# Dental_Sensor_-_CAP.net
KiCad netlist of a schematic drawn in Altium Designer
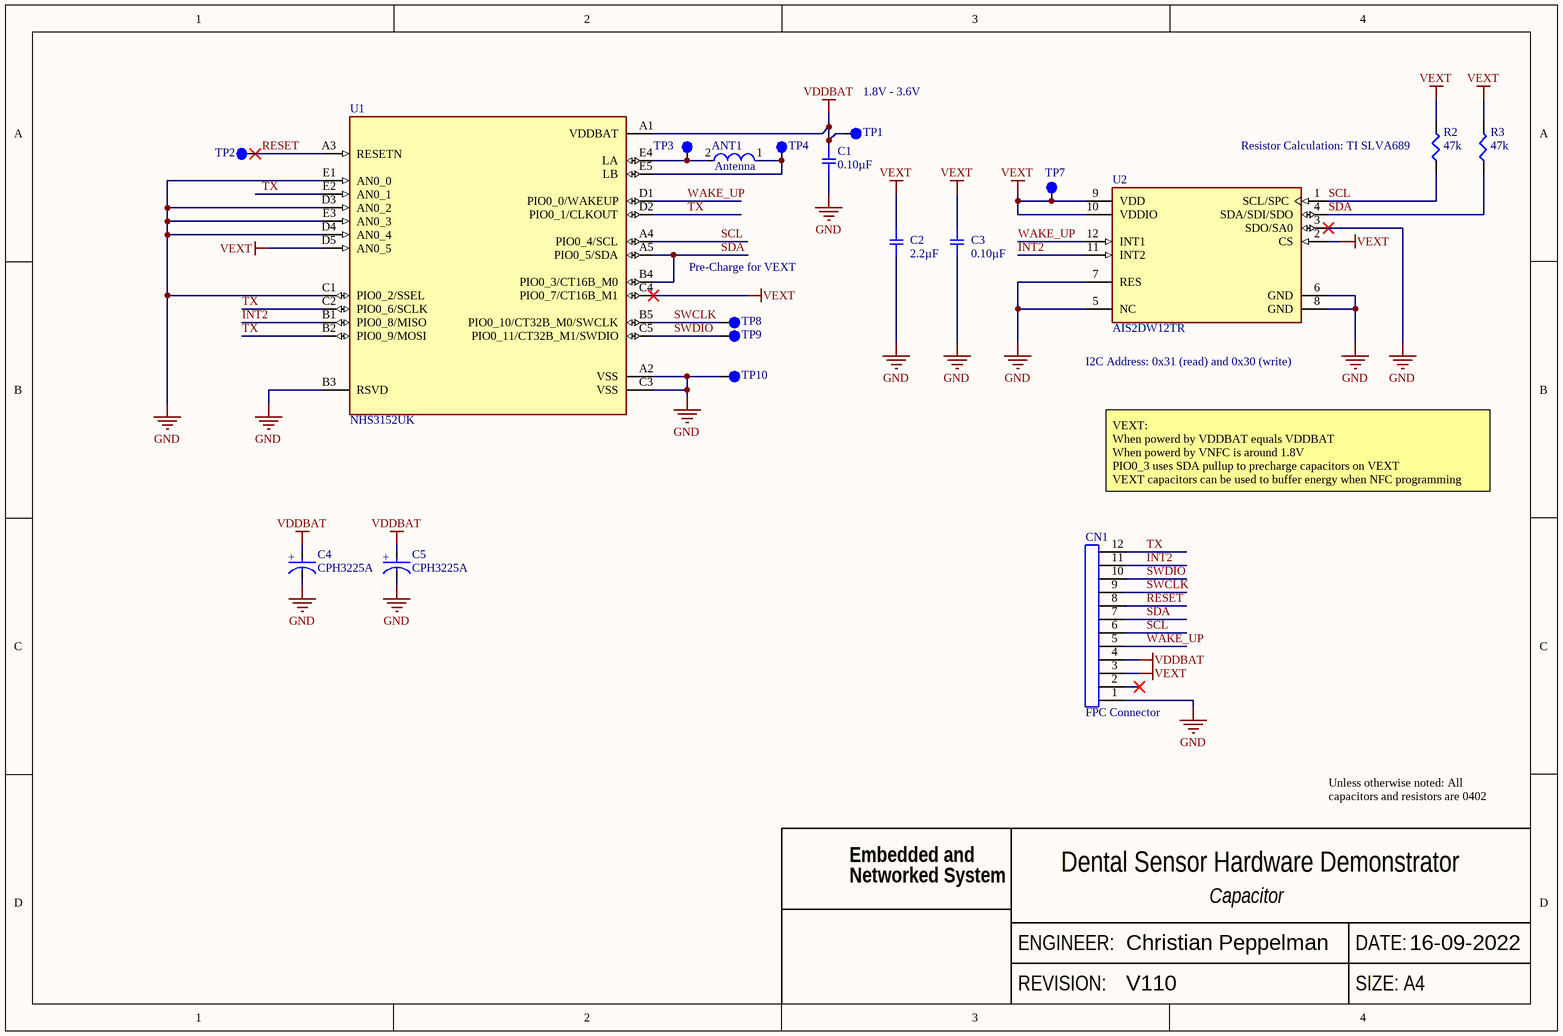
[diagram p0: Dental Sensor - CAP.SchDoc]

(export (version "E")
  (design (tool "Eeschema 10.0.6"))
  (components
    (comp (ref "ANT1")
      (value "Antenna")
      (footprint "NFC Antenna")
      (description "Track 0.2; Gap 0.1; Height 4.6; Width 14.5;")
      (libsource (lib "Library") (part "NFC Antenna"))
    )
    (comp (ref "C1")
      (value "0.10µF")
      (footprint "CAPC1005X03N")
      (description "CAP CER 0.1UF 6.3V X5R 0402")
      (fields
        (field (name "DIGI-KEY PART NUMBER") "490-6287-1-ND")
        (field (name "PART NUMBER") "GRM155R60J104KA01D")
      )
      (libsource (lib "capacitor_murata_0402") (part "GRM155R60J104KA01D"))
    )
    (comp (ref "C2")
      (value "2.2µF")
      (footprint "CAPC1005X03N")
      (description "CAP CER 2.2UF 6.3V X5R 0402")
      (fields
        (field (name "DIGI-KEY PART NUMBER") "490-12250-1-ND")
        (field (name "PART NUMBER") "GRT155R60J225KE01D")
      )
      (libsource (lib "capacitor_murata_0402") (part "GRT155R60J225KE01D"))
    )
    (comp (ref "C3")
      (value "0.10µF")
      (footprint "CAPC1005X03N")
      (description "CAP CER 0.1UF 6.3V X5R 0402")
      (fields
        (field (name "DIGI-KEY PART NUMBER") "490-6287-1-ND")
        (field (name "PART NUMBER") "GRM155R60J104KA01D")
      )
      (libsource (lib "capacitor_murata_0402") (part "GRM155R60J104KA01D"))
    )
    (comp (ref "C4")
      (value "CPH3225A")
      (footprint "CPH3225A")
      (description "Supercapacitors / Ultracapacitors Reflow EDLC 3.3V, 11mF, 160 Ohm")
      (libsource (lib "Library") (part "CPH3225A"))
    )
    (comp (ref "C5")
      (value "CPH3225A")
      (footprint "CPH3225A")
      (description "Supercapacitors / Ultracapacitors Reflow EDLC 3.3V, 11mF, 160 Ohm")
      (libsource (lib "Library") (part "CPH3225A"))
    )
    (comp (ref "CN1")
      (value "FPC Connector")
      (footprint "52745-1297")
      (description "FFC / FPC Board Connector, 0.5 mm, 12 Contacts, Receptacle, Easy-On 52745, Surface Mount, Top")
      (libsource (lib "Library") (part "52745-1297"))
    )
    (comp (ref "R2")
      (value "47k")
      (footprint "RESC1005X03N")
      (description "RES SMD 47K OHM 1% 1/10W 0402")
      (fields
        (field (name "PART NUMBER") "ERJ-2RKF4702X")
        (field (name "DIGI-KEY PART NUMBER") "P47.0KLCT-ND")
      )
      (libsource (lib "Panasonic_ERJ_0402") (part "ERJ-2RKF4702X"))
    )
    (comp (ref "R3")
      (value "47k")
      (footprint "RESC1005X03N")
      (description "RES SMD 47K OHM 1% 1/10W 0402")
      (fields
        (field (name "PART NUMBER") "ERJ-2RKF4702X")
        (field (name "DIGI-KEY PART NUMBER") "P47.0KLCT-ND")
      )
      (libsource (lib "Panasonic_ERJ_0402") (part "ERJ-2RKF4702X"))
    )
    (comp (ref "TP1")
      (value "Testpoint")
      (footprint "Testpoint 0.35mm")
      (libsource (lib "Library") (part "Testpoint"))
    )
    (comp (ref "TP2")
      (value "Testpoint")
      (footprint "Testpoint 0.35mm")
      (libsource (lib "Library") (part "Testpoint"))
    )
    (comp (ref "TP3")
      (value "Testpoint")
      (footprint "Testpoint 0.35mm")
      (libsource (lib "Library") (part "Testpoint"))
    )
    (comp (ref "TP4")
      (value "Testpoint")
      (footprint "Testpoint 0.35mm")
      (libsource (lib "Library") (part "Testpoint"))
    )
    (comp (ref "TP7")
      (value "Testpoint")
      (footprint "Testpoint 0.35mm")
      (libsource (lib "Library") (part "Testpoint"))
    )
    (comp (ref "TP8")
      (value "Testpoint")
      (footprint "Testpoint 0.35mm")
      (libsource (lib "Library") (part "Testpoint"))
    )
    (comp (ref "TP9")
      (value "Testpoint")
      (footprint "Testpoint 0.35mm")
      (libsource (lib "Library") (part "Testpoint"))
    )
    (comp (ref "TP10")
      (value "Testpoint")
      (footprint "Testpoint 0.35mm")
      (libsource (lib "Library") (part "Testpoint"))
    )
    (comp (ref "U1")
      (value "NHS3152UK")
      (footprint "WLCSP25")
      (description "ARM-microcontrollers - MCU NTAG NHS3152 NFC")
      (libsource (lib "Library") (part "NHS3152UK"))
    )
    (comp (ref "U2")
      (value "AIS2DW12TR")
      (footprint "FP-LGA12-DM00369449-MFG")
      (description "MEMS DIGITAL OUTPUT MOTION SENSO")
      (libsource (lib "Altium Content Vault") (part "7c84b71c388d4f21c3e092307226021"))
    )
  )
  (nets
    (net (code "1") (name "/INT2") (class "Default")
      (node (ref "CN1") (pin "11") (pintype "passive"))
      (node (ref "U1") (pin "B1") (pinfunction "PIO0_8/MISO_B1") (pintype "bidirectional"))
      (node (ref "U2") (pin "11") (pinfunction "INT2_11") (pintype "input"))
    )
    (net (code "2") (name "/RESET") (class "Default")
      (node (ref "CN1") (pin "8") (pintype "passive"))
      (node (ref "TP2") (pin "1") (pinfunction "2_1") (pintype "passive"))
      (node (ref "U1") (pin "A3") (pinfunction "RESETN_A3") (pintype "input"))
    )
    (net (code "3") (name "/SCL") (class "Default")
      (node (ref "CN1") (pin "6") (pintype "passive"))
      (node (ref "R2") (pin "1") (pinfunction "1_1") (pintype "passive"))
      (node (ref "U1") (pin "A4") (pinfunction "PIO0_4/SCL_A4") (pintype "bidirectional"))
      (node (ref "U2") (pin "1") (pinfunction "SCL/SPC_1") (pintype "input"))
    )
    (net (code "4") (name "/SDA") (class "Default")
      (node (ref "CN1") (pin "7") (pintype "passive"))
      (node (ref "R3") (pin "1") (pinfunction "1_1") (pintype "passive"))
      (node (ref "U1") (pin "A5") (pinfunction "PIO0_5/SDA_A5") (pintype "bidirectional"))
      (node (ref "U1") (pin "B4") (pinfunction "PIO0_3/CT16B_M0_B4") (pintype "bidirectional"))
      (node (ref "U2") (pin "4") (pinfunction "SDA/SDI/SDO_4") (pintype "bidirectional"))
    )
    (net (code "5") (name "/SWCLK") (class "Default")
      (node (ref "CN1") (pin "9") (pintype "passive"))
      (node (ref "TP8") (pin "1") (pinfunction "2_1") (pintype "passive"))
      (node (ref "U1") (pin "B5") (pinfunction "PIO0_10/CT32B_M0/SWCLK_B5") (pintype "bidirectional"))
    )
    (net (code "6") (name "/SWDIO") (class "Default")
      (node (ref "CN1") (pin "10") (pintype "passive"))
      (node (ref "TP9") (pin "1") (pinfunction "2_1") (pintype "passive"))
      (node (ref "U1") (pin "C5") (pinfunction "PIO0_11/CT32B_M1/SWDIO_C5") (pintype "bidirectional"))
    )
    (net (code "7") (name "/TX") (class "Default")
      (node (ref "CN1") (pin "12") (pintype "passive"))
      (node (ref "U1") (pin "B2") (pinfunction "PIO0_9/MOSI_B2") (pintype "bidirectional"))
      (node (ref "U1") (pin "C2") (pinfunction "PIO0_6/SCLK_C2") (pintype "bidirectional"))
      (node (ref "U1") (pin "D2") (pinfunction "PIO0_1/CLKOUT_D2") (pintype "bidirectional"))
      (node (ref "U1") (pin "E2") (pinfunction "AN0_1_E2") (pintype "input"))
    )
    (net (code "8") (name "/WAKE_UP") (class "Default")
      (node (ref "CN1") (pin "5") (pintype "passive"))
      (node (ref "U1") (pin "D1") (pinfunction "PIO0_0/WAKEUP_D1") (pintype "bidirectional"))
      (node (ref "U2") (pin "12") (pinfunction "INT1_12") (pintype "input"))
    )
    (net (code "9") (name "GND") (class "Default")
      (node (ref "C1") (pin "2") (pinfunction "2_2") (pintype "passive"))
      (node (ref "C2") (pin "2") (pinfunction "2_2") (pintype "passive"))
      (node (ref "C3") (pin "2") (pinfunction "2_2") (pintype "passive"))
      (node (ref "C4") (pin "2") (pinfunction "A_2") (pintype "passive"))
      (node (ref "C5") (pin "2") (pinfunction "A_2") (pintype "passive"))
      (node (ref "CN1") (pin "1") (pintype "passive"))
      (node (ref "TP10") (pin "1") (pinfunction "2_1") (pintype "passive"))
      (node (ref "U1") (pin "A2") (pinfunction "VSS_A2") (pintype "power_in"))
      (node (ref "U1") (pin "B3") (pinfunction "RSVD_B3") (pintype "passive"))
      (node (ref "U1") (pin "C1") (pinfunction "PIO0_2/SSEL_C1") (pintype "bidirectional"))
      (node (ref "U1") (pin "C3") (pinfunction "VSS_C3") (pintype "power_in"))
      (node (ref "U1") (pin "D3") (pinfunction "AN0_2_D3") (pintype "input"))
      (node (ref "U1") (pin "D4") (pinfunction "AN0_4_D4") (pintype "input"))
      (node (ref "U1") (pin "E1") (pinfunction "AN0_0_E1") (pintype "input"))
      (node (ref "U1") (pin "E3") (pinfunction "AN0_3_E3") (pintype "input"))
      (node (ref "U2") (pin "3") (pinfunction "SDO/SA0_3") (pintype "bidirectional"))
      (node (ref "U2") (pin "5") (pinfunction "NC_5") (pintype "passive"))
      (node (ref "U2") (pin "6") (pinfunction "GND_6") (pintype "power_in"))
      (node (ref "U2") (pin "7") (pinfunction "RES_7") (pintype "passive"))
      (node (ref "U2") (pin "8") (pinfunction "GND_8") (pintype "power_in"))
    )
    (net (code "10") (name "Net-(TP3-2)") (class "Default")
      (node (ref "ANT1") (pin "2") (pinfunction "2_2") (pintype "passive"))
      (node (ref "TP3") (pin "1") (pinfunction "2_1") (pintype "passive"))
      (node (ref "U1") (pin "E4") (pinfunction "LA_E4") (pintype "bidirectional"))
    )
    (net (code "11") (name "Net-(TP4-2)") (class "Default")
      (node (ref "ANT1") (pin "1") (pinfunction "1_1") (pintype "passive"))
      (node (ref "TP4") (pin "1") (pinfunction "2_1") (pintype "passive"))
      (node (ref "U1") (pin "E5") (pinfunction "LB_E5") (pintype "bidirectional"))
    )
    (net (code "12") (name "VDDBAT") (class "Default")
      (node (ref "C1") (pin "1") (pinfunction "1_1") (pintype "passive"))
      (node (ref "C4") (pin "1") (pinfunction "C_1") (pintype "passive"))
      (node (ref "C5") (pin "1") (pinfunction "C_1") (pintype "passive"))
      (node (ref "CN1") (pin "4") (pintype "passive"))
      (node (ref "TP1") (pin "1") (pinfunction "2_1") (pintype "passive"))
      (node (ref "U1") (pin "A1") (pinfunction "VDDBAT_A1") (pintype "power_in"))
    )
    (net (code "13") (name "VEXT") (class "Default")
      (node (ref "C2") (pin "1") (pinfunction "1_1") (pintype "passive"))
      (node (ref "C3") (pin "1") (pinfunction "1_1") (pintype "passive"))
      (node (ref "CN1") (pin "3") (pintype "passive"))
      (node (ref "R2") (pin "2") (pinfunction "2_2") (pintype "passive"))
      (node (ref "R3") (pin "2") (pinfunction "2_2") (pintype "passive"))
      (node (ref "TP7") (pin "1") (pinfunction "2_1") (pintype "passive"))
      (node (ref "U1") (pin "C4") (pinfunction "PIO0_7/CT16B_M1_C4") (pintype "bidirectional"))
      (node (ref "U1") (pin "D5") (pinfunction "AN0_5_D5") (pintype "input"))
      (node (ref "U2") (pin "10") (pinfunction "VDDIO_10") (pintype "power_in"))
      (node (ref "U2") (pin "2") (pinfunction "CS_2") (pintype "input"))
      (node (ref "U2") (pin "9") (pinfunction "VDD_9") (pintype "power_in"))
    )
    (net (code "14") (name "unconnected-(CN1-Pad2)") (class "Default")
      (node (ref "CN1") (pin "2") (pintype "passive+no_connect"))
    )
  )
)
